# MCU.net
KiCad netlist of a schematic drawn in Altium Designer
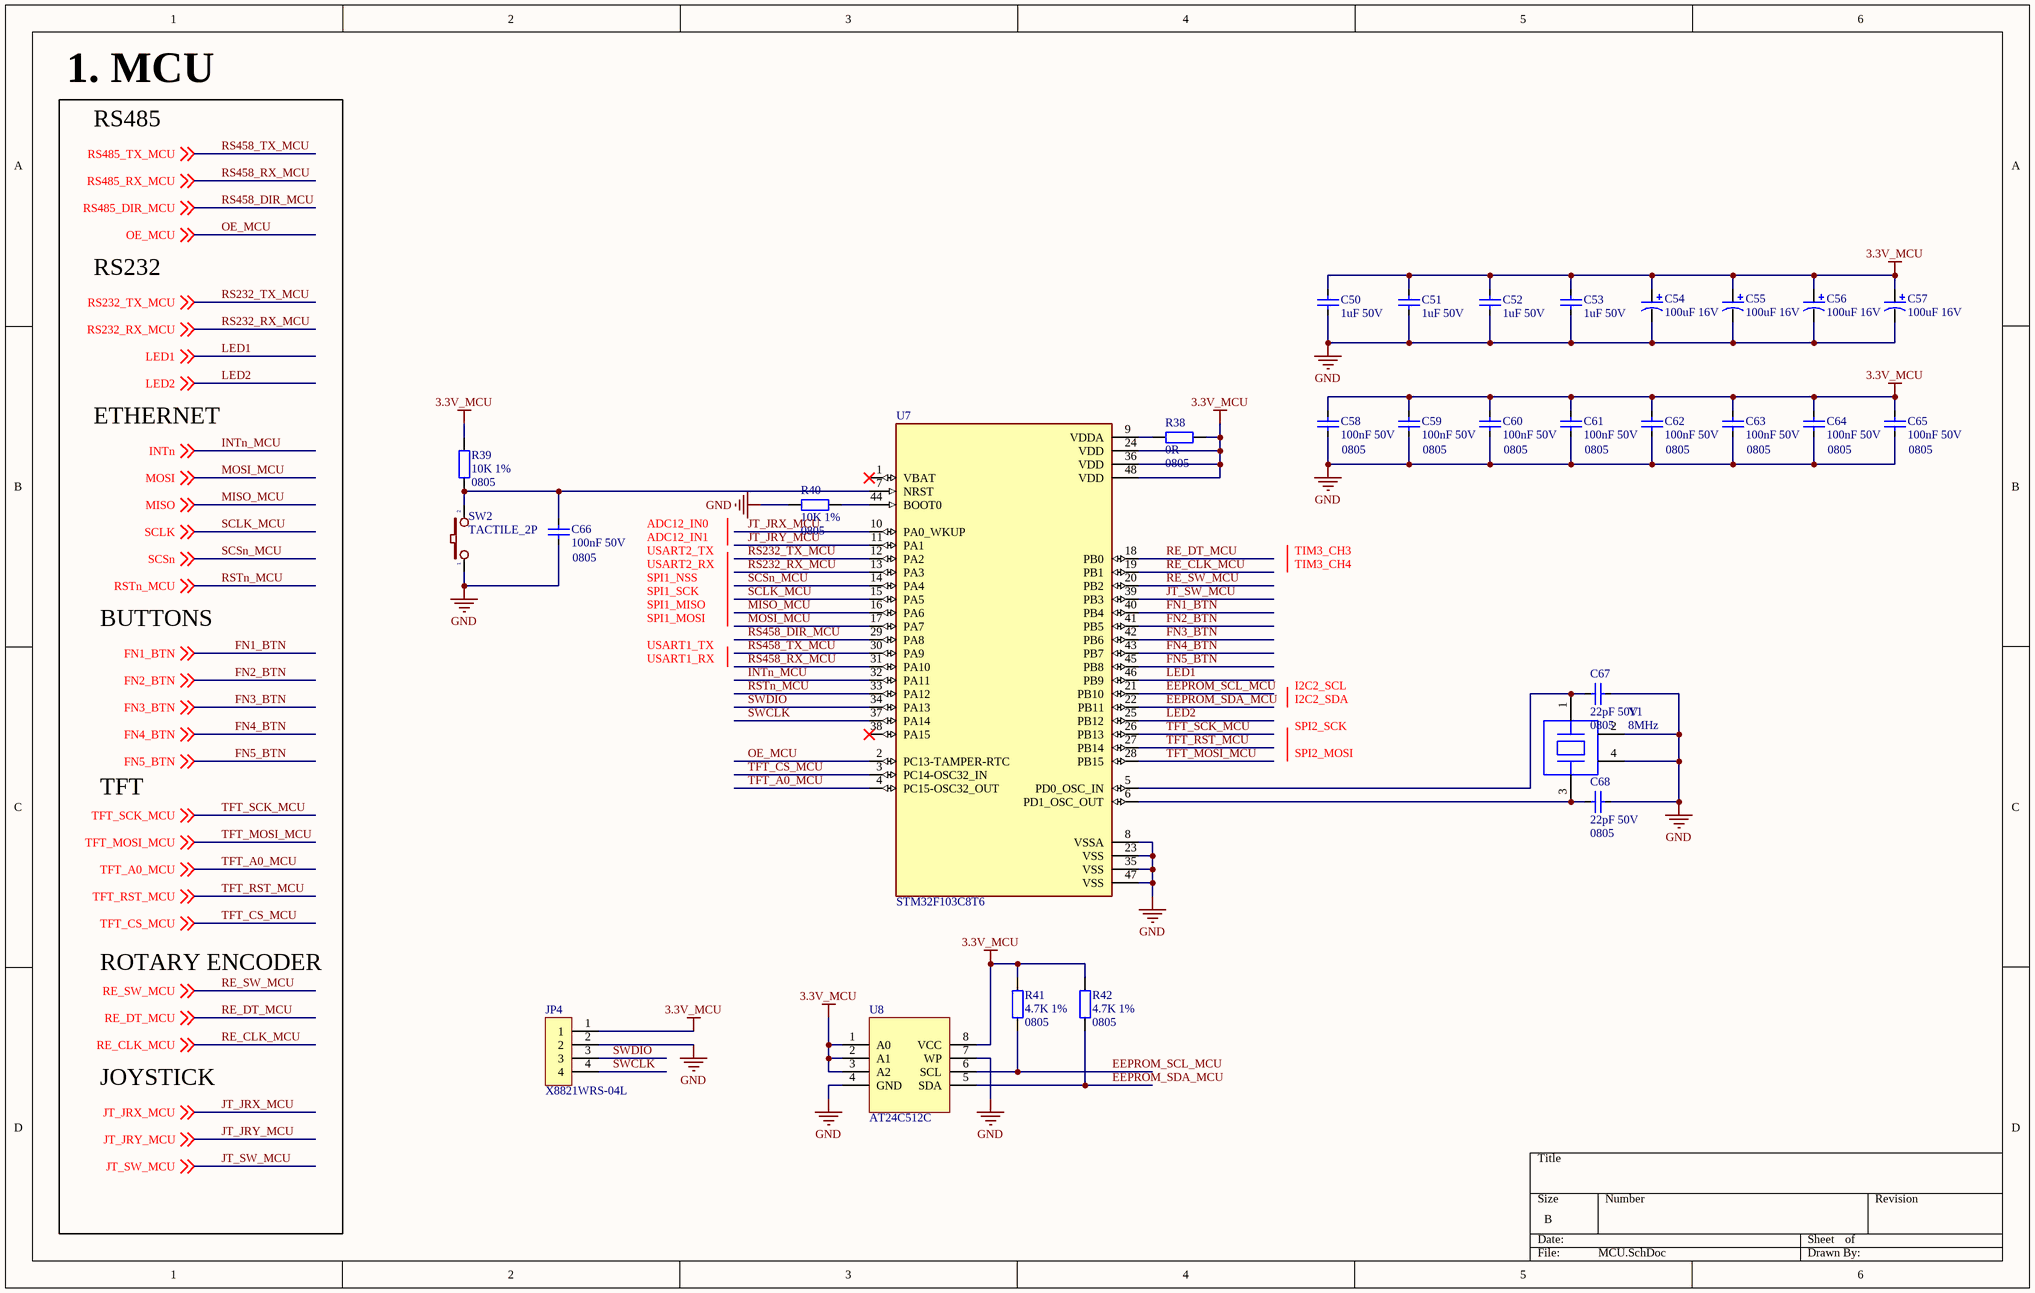
[diagram p0: MCU.SchDoc]

(export (version "E")
  (design (tool "Eeschema 10.0.6"))
  (components
    (comp (ref "C50")
      (value "1uF 50V")
      (footprint "CAP_SMD_0805")
      (description "1 µF ±10% 50V Ceramic Capacitor X7R 0805 (2012 Metric)")
      (fields
        (field (name "MANUFACTURER") "Samsung Electro-Mechanics")
        (field (name "MANUFACTURE PART NUMBER") "CL21B105KBFNNNG")
      )
      (libsource (lib "Capacitors") (part "C0805_MLCC_1uF_50V"))
    )
    (comp (ref "C51")
      (value "1uF 50V")
      (footprint "CAP_SMD_0805")
      (description "1 µF ±10% 50V Ceramic Capacitor X7R 0805 (2012 Metric)")
      (fields
        (field (name "MANUFACTURER") "Samsung Electro-Mechanics")
        (field (name "MANUFACTURE PART NUMBER") "CL21B105KBFNNNG")
      )
      (libsource (lib "Capacitors") (part "C0805_MLCC_1uF_50V"))
    )
    (comp (ref "C52")
      (value "1uF 50V")
      (footprint "CAP_SMD_0805")
      (description "1 µF ±10% 50V Ceramic Capacitor X7R 0805 (2012 Metric)")
      (fields
        (field (name "MANUFACTURER") "Samsung Electro-Mechanics")
        (field (name "MANUFACTURE PART NUMBER") "CL21B105KBFNNNG")
      )
      (libsource (lib "Capacitors") (part "C0805_MLCC_1uF_50V"))
    )
    (comp (ref "C53")
      (value "1uF 50V")
      (footprint "CAP_SMD_0805")
      (description "1 µF ±10% 50V Ceramic Capacitor X7R 0805 (2012 Metric)")
      (fields
        (field (name "MANUFACTURER") "Samsung Electro-Mechanics")
        (field (name "MANUFACTURE PART NUMBER") "CL21B105KBFNNNG")
      )
      (libsource (lib "Capacitors") (part "C0805_MLCC_1uF_50V"))
    )
    (comp (ref "C54")
      (value "100uF 16V")
      (footprint "CAP-ALU-SMD-D")
      (description "100uF 16V 63mA@120Hz ±20% SMD,D6.3xL5.4mm Aluminum Electrolytic Capacitors - SMD ROHS")
      (fields
        (field (name "MANUFACTURER") "DMBJ")
        (field (name "MANUFACTURE PART NUMBER") "RVT1C101M0605 100UF 16V")
      )
      (libsource (lib "Capacitors") (part "C_ALU_100uF_16V"))
    )
    (comp (ref "C55")
      (value "100uF 16V")
      (footprint "CAP-ALU-SMD-D")
      (description "100uF 16V 63mA@120Hz ±20% SMD,D6.3xL5.4mm Aluminum Electrolytic Capacitors - SMD ROHS")
      (fields
        (field (name "MANUFACTURER") "DMBJ")
        (field (name "MANUFACTURE PART NUMBER") "RVT1C101M0605 100UF 16V")
      )
      (libsource (lib "Capacitors") (part "C_ALU_100uF_16V"))
    )
    (comp (ref "C56")
      (value "100uF 16V")
      (footprint "CAP-ALU-SMD-D")
      (description "100uF 16V 63mA@120Hz ±20% SMD,D6.3xL5.4mm Aluminum Electrolytic Capacitors - SMD ROHS")
      (fields
        (field (name "MANUFACTURER") "DMBJ")
        (field (name "MANUFACTURE PART NUMBER") "RVT1C101M0605 100UF 16V")
      )
      (libsource (lib "Capacitors") (part "C_ALU_100uF_16V"))
    )
    (comp (ref "C57")
      (value "100uF 16V")
      (footprint "CAP-ALU-SMD-D")
      (description "100uF 16V 63mA@120Hz ±20% SMD,D6.3xL5.4mm Aluminum Electrolytic Capacitors - SMD ROHS")
      (fields
        (field (name "MANUFACTURER") "DMBJ")
        (field (name "MANUFACTURE PART NUMBER") "RVT1C101M0605 100UF 16V")
      )
      (libsource (lib "Capacitors") (part "C_ALU_100uF_16V"))
    )
    (comp (ref "C58")
      (value "100nF 50V")
      (footprint "CAP_SMD_0805")
      (description "0.1 µF ±10% 50V Ceramic Capacitor X7R 0805 (2012 Metric)")
      (fields
        (field (name "MANUFACTURER") "YAGEO")
        (field (name "MANUFACTURE PART NUMBER") "CC0805KRX7R9BB104")
        (field (name "SIZE") "0805")
      )
      (libsource (lib "Capacitors") (part "C0805_MLCC_100nF_50V"))
    )
    (comp (ref "C59")
      (value "100nF 50V")
      (footprint "CAP_SMD_0805")
      (description "0.1 µF ±10% 50V Ceramic Capacitor X7R 0805 (2012 Metric)")
      (fields
        (field (name "MANUFACTURER") "YAGEO")
        (field (name "MANUFACTURE PART NUMBER") "CC0805KRX7R9BB104")
        (field (name "SIZE") "0805")
      )
      (libsource (lib "Capacitors") (part "C0805_MLCC_100nF_50V"))
    )
    (comp (ref "C60")
      (value "100nF 50V")
      (footprint "CAP_SMD_0805")
      (description "0.1 µF ±10% 50V Ceramic Capacitor X7R 0805 (2012 Metric)")
      (fields
        (field (name "MANUFACTURER") "YAGEO")
        (field (name "MANUFACTURE PART NUMBER") "CC0805KRX7R9BB104")
        (field (name "SIZE") "0805")
      )
      (libsource (lib "Capacitors") (part "C0805_MLCC_100nF_50V"))
    )
    (comp (ref "C61")
      (value "100nF 50V")
      (footprint "CAP_SMD_0805")
      (description "0.1 µF ±10% 50V Ceramic Capacitor X7R 0805 (2012 Metric)")
      (fields
        (field (name "MANUFACTURER") "YAGEO")
        (field (name "MANUFACTURE PART NUMBER") "CC0805KRX7R9BB104")
        (field (name "SIZE") "0805")
      )
      (libsource (lib "Capacitors") (part "C0805_MLCC_100nF_50V"))
    )
    (comp (ref "C62")
      (value "100nF 50V")
      (footprint "CAP_SMD_0805")
      (description "0.1 µF ±10% 50V Ceramic Capacitor X7R 0805 (2012 Metric)")
      (fields
        (field (name "MANUFACTURER") "YAGEO")
        (field (name "MANUFACTURE PART NUMBER") "CC0805KRX7R9BB104")
        (field (name "SIZE") "0805")
      )
      (libsource (lib "Capacitors") (part "C0805_MLCC_100nF_50V"))
    )
    (comp (ref "C63")
      (value "100nF 50V")
      (footprint "CAP_SMD_0805")
      (description "0.1 µF ±10% 50V Ceramic Capacitor X7R 0805 (2012 Metric)")
      (fields
        (field (name "MANUFACTURER") "YAGEO")
        (field (name "MANUFACTURE PART NUMBER") "CC0805KRX7R9BB104")
        (field (name "SIZE") "0805")
      )
      (libsource (lib "Capacitors") (part "C0805_MLCC_100nF_50V"))
    )
    (comp (ref "C64")
      (value "100nF 50V")
      (footprint "CAP_SMD_0805")
      (description "0.1 µF ±10% 50V Ceramic Capacitor X7R 0805 (2012 Metric)")
      (fields
        (field (name "MANUFACTURER") "YAGEO")
        (field (name "MANUFACTURE PART NUMBER") "CC0805KRX7R9BB104")
        (field (name "SIZE") "0805")
      )
      (libsource (lib "Capacitors") (part "C0805_MLCC_100nF_50V"))
    )
    (comp (ref "C65")
      (value "100nF 50V")
      (footprint "CAP_SMD_0805")
      (description "0.1 µF ±10% 50V Ceramic Capacitor X7R 0805 (2012 Metric)")
      (fields
        (field (name "MANUFACTURER") "YAGEO")
        (field (name "MANUFACTURE PART NUMBER") "CC0805KRX7R9BB104")
        (field (name "SIZE") "0805")
      )
      (libsource (lib "Capacitors") (part "C0805_MLCC_100nF_50V"))
    )
    (comp (ref "C66")
      (value "100nF 50V")
      (footprint "CAP_SMD_0805")
      (description "0.1 µF ±10% 50V Ceramic Capacitor X7R 0805 (2012 Metric)")
      (fields
        (field (name "MANUFACTURER") "YAGEO")
        (field (name "MANUFACTURE PART NUMBER") "CC0805KRX7R9BB104")
        (field (name "SIZE") "0805")
      )
      (libsource (lib "Capacitors") (part "C0805_MLCC_100nF_50V"))
    )
    (comp (ref "C67")
      (value "22pF 50V")
      (footprint "CAP_SMD_0805")
      (description "22 pF ±1% 250V Ceramic Capacitor C0G, NP0 0805 (2012 Metric)")
      (fields
        (field (name "MANUFACTURER") "KYOCERA AVX")
        (field (name "MANUFACTURE PART NUMBER") "600F220FT250XT")
        (field (name "SIZE") "0805")
      )
      (libsource (lib "Capacitors") (part "C0805_MLCC_22pF_50V"))
    )
    (comp (ref "C68")
      (value "22pF 50V")
      (footprint "CAP_SMD_0805")
      (description "22 pF ±1% 250V Ceramic Capacitor C0G, NP0 0805 (2012 Metric)")
      (fields
        (field (name "MANUFACTURER") "KYOCERA AVX")
        (field (name "MANUFACTURE PART NUMBER") "600F220FT250XT")
        (field (name "SIZE") "0805")
      )
      (libsource (lib "Capacitors") (part "C0805_MLCC_22pF_50V"))
    )
    (comp (ref "JP4")
      (value "X8821WRS-04L")
      (footprint "CONN_X8821WRS-04L-LPSN")
      (fields
        (field (name "MANUFACTURER") "XKB Connection")
        (field (name "MANUFACTURE PART NUMBER") "X8821WRS-04-9TSN")
      )
      (libsource (lib "Connectors") (part "X8821WRS-04L"))
    )
    (comp (ref "R38")
      (value "0R")
      (footprint "RES_SMD_0805")
      (description "0 Ohms Jumper Chip Resistor 0805 (2012 Metric) Automotive AEC-Q200 Thick Film")
      (fields
        (field (name "MANUFACTURER") "Vishay Dale")
        (field (name "MANUFACTURE PART NUMBER") "CRCW08050000Z0EA")
        (field (name "SIZE") "0805")
      )
      (libsource (lib "Resistors") (part "R0805_0R"))
    )
    (comp (ref "R39")
      (value "10K 1%")
      (footprint "RES_SMD_0805")
      (description "10 kOhms ±1% 0.125W, 1/8W Chip Resistor 0805 (2012 Metric) Moisture Resistant Thick Film")
      (fields
        (field (name "MANUFACTURER") "YAGEO")
        (field (name "MANUFACTURE PART NUMBER") "RC0805FR-0710KL")
        (field (name "SIZE") "0805")
      )
      (libsource (lib "Resistors") (part "R0805_10K"))
    )
    (comp (ref "R40")
      (value "10K 1%")
      (footprint "RES_SMD_0805")
      (description "10 kOhms ±1% 0.125W, 1/8W Chip Resistor 0805 (2012 Metric) Moisture Resistant Thick Film")
      (fields
        (field (name "MANUFACTURER") "YAGEO")
        (field (name "MANUFACTURE PART NUMBER") "RC0805FR-0710KL")
        (field (name "SIZE") "0805")
      )
      (libsource (lib "Resistors") (part "R0805_10K"))
    )
    (comp (ref "R41")
      (value "4.7K 1%")
      (footprint "RES_SMD_0805")
      (description "4.7 kOhms ±1% 0.125W, 1/8W Chip Resistor 0805 (2012 Metric) Thick Film")
      (fields
        (field (name "MANUFACTURER") "Vishay Dale")
        (field (name "MANUFACTURE PART NUMBER") "CRCW08054K70FKEAC")
        (field (name "SIZE") "0805")
      )
      (libsource (lib "Resistors") (part "R0805_4.7K"))
    )
    (comp (ref "R42")
      (value "4.7K 1%")
      (footprint "RES_SMD_0805")
      (description "4.7 kOhms ±1% 0.125W, 1/8W Chip Resistor 0805 (2012 Metric) Thick Film")
      (fields
        (field (name "MANUFACTURER") "Vishay Dale")
        (field (name "MANUFACTURE PART NUMBER") "CRCW08054K70FKEAC")
        (field (name "SIZE") "0805")
      )
      (libsource (lib "Resistors") (part "R0805_4.7K"))
    )
    (comp (ref "SW2")
      (value "TACTILE_2P")
      (footprint "C&K BUTTON 2P")
      (description "Tactile Switch SPST-NO Top Actuated Surface Mount")
      (fields
        (field (name "MANUFACTURER") "C&K")
        (field (name "MANUFACTURE PART NUMBER") "PTS636 SM43 SMTR LFS")
      )
      (libsource (lib "Button") (part "SWITCH_TACTILE_2P"))
    )
    (comp (ref "U7")
      (value "STM32F103C8T6")
      (footprint "LQFP-48")
      (description "ARM® Cortex®-M3 STM32F1 Microcontroller IC 32-Bit Single-Core 72MHz 64KB (64K x 8) FLASH")
      (fields (field (name "MANUFACTURER") "STMicroelectronics"))
      (libsource (lib "MCU") (part "STM32F103C8T6"))
    )
    (comp (ref "U8")
      (value "AT24C512C")
      (footprint "SOIC-8")
      (description "512Kbit I2C SOIC-8 EEPROM ROHS")
      (fields
        (field (name "MANUFACTURER") "Microchip Tech")
        (field (name "MANUFACTURE PART NUMBER") "AT24C512C-SSHD-T")
      )
      (libsource (lib "ICs") (part "EEPROM_512K_AT24C512C"))
    )
    (comp (ref "Y1")
      (value "8MHz")
      (footprint "SMD-3225_4P")
      (description "8MHz 贴片晶振 12pF ±10ppm ±20ppm SMD3225-4P Crystals ROHS")
      (fields
        (field (name "MANUFACTURER") "YXC Crystal Oscillators")
        (field (name "MANUFACTURE PART NUMBER") "X32258MOB4SI")
      )
      (libsource (lib "Crystal") (part "C3225_8MHz"))
    )
  )
  (nets
    (net (code "1") (name "/EEPROM_SCL_MCU") (class "Default")
      (node (ref "R41") (pin "1") (pinfunction "1_1") (pintype "passive"))
      (node (ref "U7") (pin "21") (pinfunction "PB10_21") (pintype "bidirectional"))
      (node (ref "U8") (pin "6") (pinfunction "SCL_6") (pintype "passive"))
    )
    (net (code "2") (name "/EEPROM_SDA_MCU") (class "Default")
      (node (ref "R42") (pin "1") (pinfunction "1_1") (pintype "passive"))
      (node (ref "U7") (pin "22") (pinfunction "PB11_22") (pintype "bidirectional"))
      (node (ref "U8") (pin "5") (pinfunction "SDA_5") (pintype "passive"))
    )
    (net (code "3") (name "/SWCLK") (class "Default")
      (node (ref "JP4") (pin "4") (pinfunction "4_4") (pintype "passive"))
      (node (ref "U7") (pin "37") (pinfunction "PA14_37") (pintype "bidirectional"))
    )
    (net (code "4") (name "/SWDIO") (class "Default")
      (node (ref "JP4") (pin "3") (pinfunction "3_3") (pintype "passive"))
      (node (ref "U7") (pin "34") (pinfunction "PA13_34") (pintype "bidirectional"))
    )
    (net (code "5") (name "3.3V_MCU") (class "Default")
      (node (ref "C50") (pin "2") (pinfunction "2_2") (pintype "passive"))
      (node (ref "C51") (pin "2") (pinfunction "2_2") (pintype "passive"))
      (node (ref "C52") (pin "2") (pinfunction "2_2") (pintype "passive"))
      (node (ref "C53") (pin "2") (pinfunction "2_2") (pintype "passive"))
      (node (ref "C54") (pin "1") (pinfunction "1_1") (pintype "passive"))
      (node (ref "C55") (pin "1") (pinfunction "1_1") (pintype "passive"))
      (node (ref "C56") (pin "1") (pinfunction "1_1") (pintype "passive"))
      (node (ref "C57") (pin "1") (pinfunction "1_1") (pintype "passive"))
      (node (ref "C58") (pin "2") (pinfunction "2_2") (pintype "passive"))
      (node (ref "C59") (pin "2") (pinfunction "2_2") (pintype "passive"))
      (node (ref "C60") (pin "2") (pinfunction "2_2") (pintype "passive"))
      (node (ref "C61") (pin "2") (pinfunction "2_2") (pintype "passive"))
      (node (ref "C62") (pin "2") (pinfunction "2_2") (pintype "passive"))
      (node (ref "C63") (pin "2") (pinfunction "2_2") (pintype "passive"))
      (node (ref "C64") (pin "2") (pinfunction "2_2") (pintype "passive"))
      (node (ref "C65") (pin "2") (pinfunction "2_2") (pintype "passive"))
      (node (ref "JP4") (pin "1") (pinfunction "1_1") (pintype "passive"))
      (node (ref "R38") (pin "2") (pinfunction "2_2") (pintype "passive"))
      (node (ref "R39") (pin "2") (pinfunction "2_2") (pintype "passive"))
      (node (ref "R41") (pin "2") (pinfunction "2_2") (pintype "passive"))
      (node (ref "R42") (pin "2") (pinfunction "2_2") (pintype "passive"))
      (node (ref "U7") (pin "24") (pinfunction "VDD_24") (pintype "power_in"))
      (node (ref "U7") (pin "36") (pinfunction "VDD_36") (pintype "power_in"))
      (node (ref "U7") (pin "48") (pinfunction "VDD_48") (pintype "power_in"))
      (node (ref "U8") (pin "1") (pinfunction "A0_1") (pintype "passive"))
      (node (ref "U8") (pin "2") (pinfunction "A1_2") (pintype "passive"))
      (node (ref "U8") (pin "3") (pinfunction "A2_3") (pintype "passive"))
      (node (ref "U8") (pin "8") (pinfunction "VCC_8") (pintype "passive"))
    )
    (net (code "6") (name "FN1_BTN") (class "Default")
      (node (ref "U7") (pin "40") (pinfunction "PB4_40") (pintype "bidirectional"))
    )
    (net (code "7") (name "FN2_BTN") (class "Default")
      (node (ref "U7") (pin "41") (pinfunction "PB5_41") (pintype "bidirectional"))
    )
    (net (code "8") (name "FN3_BTN") (class "Default")
      (node (ref "U7") (pin "42") (pinfunction "PB6_42") (pintype "bidirectional"))
    )
    (net (code "9") (name "FN4_BTN") (class "Default")
      (node (ref "U7") (pin "43") (pinfunction "PB7_43") (pintype "bidirectional"))
    )
    (net (code "10") (name "FN5_BTN") (class "Default")
      (node (ref "U7") (pin "45") (pinfunction "PB8_45") (pintype "bidirectional"))
    )
    (net (code "11") (name "GND") (class "Default")
      (node (ref "C50") (pin "1") (pinfunction "1_1") (pintype "passive"))
      (node (ref "C51") (pin "1") (pinfunction "1_1") (pintype "passive"))
      (node (ref "C52") (pin "1") (pinfunction "1_1") (pintype "passive"))
      (node (ref "C53") (pin "1") (pinfunction "1_1") (pintype "passive"))
      (node (ref "C54") (pin "2") (pinfunction "2_2") (pintype "passive"))
      (node (ref "C55") (pin "2") (pinfunction "2_2") (pintype "passive"))
      (node (ref "C56") (pin "2") (pinfunction "2_2") (pintype "passive"))
      (node (ref "C57") (pin "2") (pinfunction "2_2") (pintype "passive"))
      (node (ref "C58") (pin "1") (pinfunction "1_1") (pintype "passive"))
      (node (ref "C59") (pin "1") (pinfunction "1_1") (pintype "passive"))
      (node (ref "C60") (pin "1") (pinfunction "1_1") (pintype "passive"))
      (node (ref "C61") (pin "1") (pinfunction "1_1") (pintype "passive"))
      (node (ref "C62") (pin "1") (pinfunction "1_1") (pintype "passive"))
      (node (ref "C63") (pin "1") (pinfunction "1_1") (pintype "passive"))
      (node (ref "C64") (pin "1") (pinfunction "1_1") (pintype "passive"))
      (node (ref "C65") (pin "1") (pinfunction "1_1") (pintype "passive"))
      (node (ref "C66") (pin "1") (pinfunction "1_1") (pintype "passive"))
      (node (ref "C67") (pin "1") (pinfunction "1_1") (pintype "passive"))
      (node (ref "C68") (pin "1") (pinfunction "1_1") (pintype "passive"))
      (node (ref "JP4") (pin "2") (pinfunction "2_2") (pintype "passive"))
      (node (ref "R40") (pin "1") (pinfunction "1_1") (pintype "passive"))
      (node (ref "SW2") (pin "1") (pinfunction "1_1") (pintype "passive"))
      (node (ref "U7") (pin "23") (pinfunction "VSS_23") (pintype "power_in"))
      (node (ref "U7") (pin "35") (pinfunction "VSS_35") (pintype "power_in"))
      (node (ref "U7") (pin "47") (pinfunction "VSS_47") (pintype "power_in"))
      (node (ref "U7") (pin "8") (pinfunction "VSSA_8") (pintype "power_in"))
      (node (ref "U8") (pin "4") (pinfunction "GND_4") (pintype "passive"))
      (node (ref "U8") (pin "7") (pinfunction "WP_7") (pintype "passive"))
      (node (ref "Y1") (pin "2") (pinfunction "2_2") (pintype "passive"))
      (node (ref "Y1") (pin "4") (pinfunction "4_4") (pintype "passive"))
    )
    (net (code "12") (name "INTn") (class "Default")
      (node (ref "U7") (pin "32") (pinfunction "PA11_32") (pintype "bidirectional"))
    )
    (net (code "13") (name "JT_JRX_MCU") (class "Default")
      (node (ref "U7") (pin "10") (pinfunction "PA0_WKUP_10") (pintype "bidirectional"))
    )
    (net (code "14") (name "JT_JRY_MCU") (class "Default")
      (node (ref "U7") (pin "11") (pinfunction "PA1_11") (pintype "bidirectional"))
    )
    (net (code "15") (name "JT_SW_MCU") (class "Default")
      (node (ref "U7") (pin "39") (pinfunction "PB3_39") (pintype "bidirectional"))
    )
    (net (code "16") (name "LED1") (class "Default")
      (node (ref "U7") (pin "46") (pinfunction "PB9_46") (pintype "bidirectional"))
    )
    (net (code "17") (name "LED2") (class "Default")
      (node (ref "U7") (pin "25") (pinfunction "PB12_25") (pintype "bidirectional"))
    )
    (net (code "18") (name "MISO") (class "Default")
      (node (ref "U7") (pin "16") (pinfunction "PA6_16") (pintype "bidirectional"))
    )
    (net (code "19") (name "MOSI") (class "Default")
      (node (ref "U7") (pin "17") (pinfunction "PA7_17") (pintype "bidirectional"))
    )
    (net (code "20") (name "Net-(U7-BOOT0)") (class "Default")
      (node (ref "R40") (pin "2") (pinfunction "2_2") (pintype "passive"))
      (node (ref "U7") (pin "44") (pinfunction "BOOT0_44") (pintype "input"))
    )
    (net (code "21") (name "Net-(U7-NRST)") (class "Default")
      (node (ref "C66") (pin "2") (pinfunction "2_2") (pintype "passive"))
      (node (ref "R39") (pin "1") (pinfunction "1_1") (pintype "passive"))
      (node (ref "SW2") (pin "2") (pinfunction "2_2") (pintype "passive"))
      (node (ref "U7") (pin "7") (pinfunction "NRST_7") (pintype "input"))
    )
    (net (code "22") (name "Net-(U7-PD0_OSC_IN)") (class "Default")
      (node (ref "C67") (pin "2") (pinfunction "2_2") (pintype "passive"))
      (node (ref "U7") (pin "5") (pinfunction "PD0_OSC_IN_5") (pintype "bidirectional"))
      (node (ref "Y1") (pin "1") (pinfunction "1_1") (pintype "passive"))
    )
    (net (code "23") (name "Net-(U7-PD1_OSC_OUT)") (class "Default")
      (node (ref "C68") (pin "2") (pinfunction "2_2") (pintype "passive"))
      (node (ref "U7") (pin "6") (pinfunction "PD1_OSC_OUT_6") (pintype "bidirectional"))
      (node (ref "Y1") (pin "3") (pinfunction "3_3") (pintype "passive"))
    )
    (net (code "24") (name "Net-(U7-VDDA)") (class "Default")
      (node (ref "R38") (pin "1") (pinfunction "1_1") (pintype "passive"))
      (node (ref "U7") (pin "9") (pinfunction "VDDA_9") (pintype "power_in"))
    )
    (net (code "25") (name "OE_MCU") (class "Default")
      (node (ref "U7") (pin "2") (pinfunction "PC13-TAMPER-RTC_2") (pintype "bidirectional"))
    )
    (net (code "26") (name "RE_CLK_MCU") (class "Default")
      (node (ref "U7") (pin "19") (pinfunction "PB1_19") (pintype "bidirectional"))
    )
    (net (code "27") (name "RE_DT_MCU") (class "Default")
      (node (ref "U7") (pin "18") (pinfunction "PB0_18") (pintype "bidirectional"))
    )
    (net (code "28") (name "RE_SW_MCU") (class "Default")
      (node (ref "U7") (pin "20") (pinfunction "PB2_20") (pintype "bidirectional"))
    )
    (net (code "29") (name "RS232_RX_MCU") (class "Default")
      (node (ref "U7") (pin "13") (pinfunction "PA3_13") (pintype "bidirectional"))
    )
    (net (code "30") (name "RS232_TX_MCU") (class "Default")
      (node (ref "U7") (pin "12") (pinfunction "PA2_12") (pintype "bidirectional"))
    )
    (net (code "31") (name "RS485_DIR_MCU") (class "Default")
      (node (ref "U7") (pin "29") (pinfunction "PA8_29") (pintype "bidirectional"))
    )
    (net (code "32") (name "RS485_RX_MCU") (class "Default")
      (node (ref "U7") (pin "31") (pinfunction "PA10_31") (pintype "bidirectional"))
    )
    (net (code "33") (name "RS485_TX_MCU") (class "Default")
      (node (ref "U7") (pin "30") (pinfunction "PA9_30") (pintype "bidirectional"))
    )
    (net (code "34") (name "RSTn_MCU") (class "Default")
      (node (ref "U7") (pin "33") (pinfunction "PA12_33") (pintype "bidirectional"))
    )
    (net (code "35") (name "SCLK") (class "Default")
      (node (ref "U7") (pin "15") (pinfunction "PA5_15") (pintype "bidirectional"))
    )
    (net (code "36") (name "SCSn") (class "Default")
      (node (ref "U7") (pin "14") (pinfunction "PA4_14") (pintype "bidirectional"))
    )
    (net (code "37") (name "TFT_A0_MCU") (class "Default")
      (node (ref "U7") (pin "4") (pinfunction "PC15-OSC32_OUT_4") (pintype "bidirectional"))
    )
    (net (code "38") (name "TFT_CS_MCU") (class "Default")
      (node (ref "U7") (pin "3") (pinfunction "PC14-OSC32_IN_3") (pintype "bidirectional"))
    )
    (net (code "39") (name "TFT_MOSI_MCU") (class "Default")
      (node (ref "U7") (pin "28") (pinfunction "PB15_28") (pintype "bidirectional"))
    )
    (net (code "40") (name "TFT_RST_MCU") (class "Default")
      (node (ref "U7") (pin "27") (pinfunction "PB14_27") (pintype "bidirectional"))
    )
    (net (code "41") (name "TFT_SCK_MCU") (class "Default")
      (node (ref "U7") (pin "26") (pinfunction "PB13_26") (pintype "bidirectional"))
    )
    (net (code "42") (name "unconnected-(U7-PA15-Pad38)") (class "Default")
      (node (ref "U7") (pin "38") (pinfunction "PA15_38") (pintype "bidirectional+no_connect"))
    )
    (net (code "43") (name "unconnected-(U7-VBAT-Pad1)") (class "Default")
      (node (ref "U7") (pin "1") (pinfunction "VBAT_1") (pintype "bidirectional+no_connect"))
    )
  )
)
